# Oscillator_11_0592MHz_Using_HC49S.net
KiCad netlist of a schematic drawn in Altium Designer
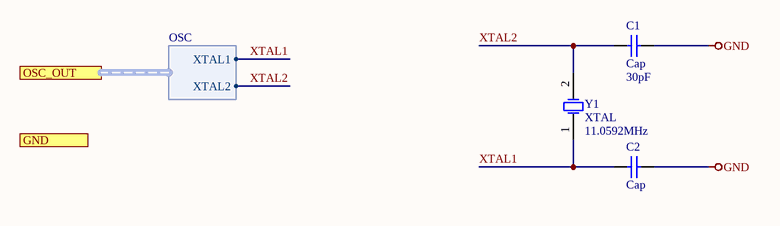
[diagram p0: Oscillator_11.0592MHz_Using_HC49S.SchDoc]

(export (version "E")
  (design (tool "Eeschema 10.0.6"))
  (components
    (comp (ref "C1")
      (value "Cap")
      (footprint "C0805")
      (description "Non-Polar Capacitor")
      (fields (field (name "ALTIUM_VALUE") "30pF"))
      (libsource (lib "Integrated_Library") (part "Cap"))
    )
    (comp (ref "C2")
      (value "Cap")
      (footprint "C0805")
      (description "Non-Polar Capacitor")
      (libsource (lib "Integrated_Library") (part "Cap"))
    )
    (comp (ref "Y1")
      (value "XTAL")
      (footprint "XTAL-HC49S-SMD")
      (description "Crystal Oscillator")
      (fields (field (name "OSCILLATIONFREQUENCY") "11.0592MHz"))
      (libsource (lib "Integrated_Library") (part "XTAL_1"))
    )
  )
  (nets
    (net (code "2") (name "/XTAL1") (class "Default")
      (node (ref "C2") (pin "1") (pinfunction "1_1") (pintype "passive"))
      (node (ref "Y1") (pin "1") (pinfunction "OSC1_1") (pintype "passive"))
    )
    (net (code "3") (name "/XTAL2") (class "Default")
      (node (ref "C1") (pin "1") (pinfunction "1_1") (pintype "passive"))
      (node (ref "Y1") (pin "2") (pinfunction "OSC2_2") (pintype "passive"))
    )
    (net (code "5") (name "GND") (class "Default")
      (node (ref "C1") (pin "2") (pinfunction "2_2") (pintype "passive"))
      (node (ref "C2") (pin "2") (pinfunction "2_2") (pintype "passive"))
    )
  )
)
